# 2_-_IO_Socket_0.net
KiCad netlist of a schematic drawn in Altium Designer
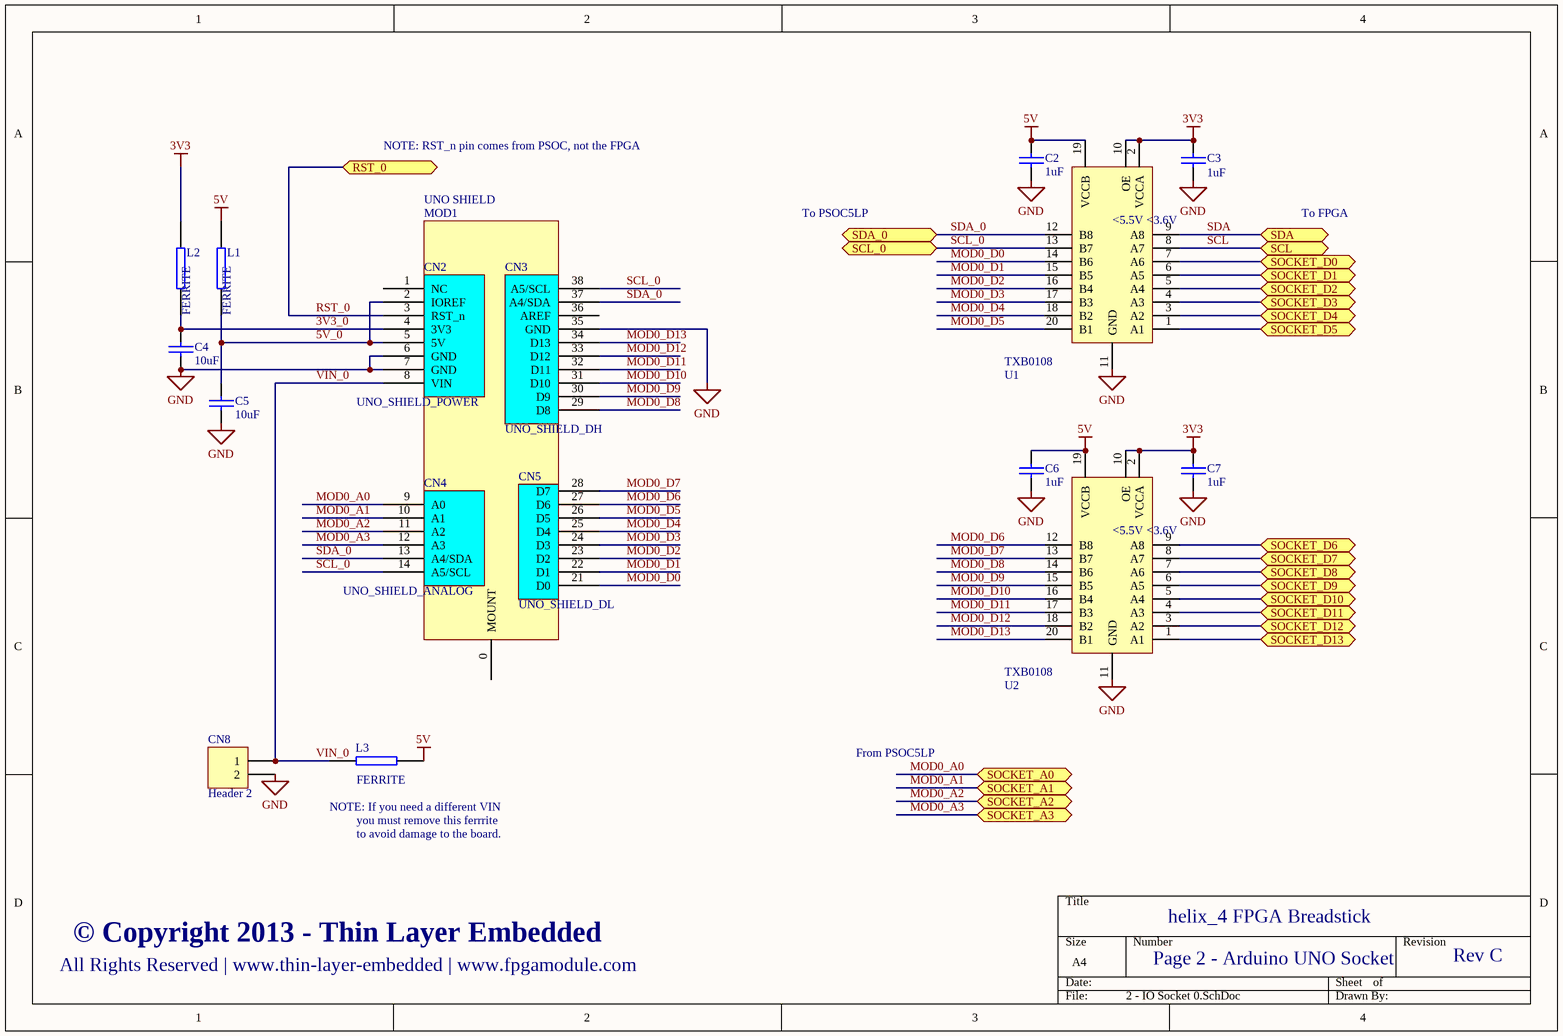
[diagram p0: 2 - IO Socket 0.SchDoc]

(export (version "E")
  (design (tool "Eeschema 10.0.6"))
  (components
    (comp (ref "C2")
      (value "1uF")
      (footprint "0805")
      (description "Capacitor")
      (libsource (lib "*") (part "CAP"))
    )
    (comp (ref "C3")
      (value "1uF")
      (footprint "0805")
      (description "Capacitor")
      (libsource (lib "*") (part "CAP"))
    )
    (comp (ref "C4")
      (value "10uF")
      (footprint "0805")
      (description "Capacitor")
      (libsource (lib "*") (part "CAP"))
    )
    (comp (ref "C5")
      (value "10uF")
      (footprint "0805")
      (description "Capacitor")
      (libsource (lib "*") (part "CAP"))
    )
    (comp (ref "C6")
      (value "1uF")
      (footprint "0805")
      (description "Capacitor")
      (libsource (lib "*") (part "CAP"))
    )
    (comp (ref "C7")
      (value "1uF")
      (footprint "0805")
      (description "Capacitor")
      (libsource (lib "*") (part "CAP"))
    )
    (comp (ref "CN2")
      (value "UNO_SHIELD_POWER")
      (footprint "UNO_SHIELD_POWER")
      (libsource (lib "master_library") (part "UNO_SHIELD_POWER"))
    )
    (comp (ref "CN3")
      (value "UNO_SHIELD_DH")
      (footprint "UNO_SHIELD_DH")
      (libsource (lib "master_library") (part "UNO_SHIELD_DH"))
    )
    (comp (ref "CN4")
      (value "UNO_SHIELD_ANALOG")
      (footprint "UNO_SHIELD_ANALOG")
      (libsource (lib "master_library") (part "UNO_SHIELD_ANALOG"))
    )
    (comp (ref "CN5")
      (value "UNO_SHIELD_DL")
      (footprint "UNO_SHIELD_DL")
      (libsource (lib "master_library") (part "UNO_SHIELD_DL"))
    )
    (comp (ref "CN8")
      (value "Header 2")
      (footprint "HDR1X2")
      (description "Header, 2-Pin")
      (fields (field (name "PUBLISHER") "Altium Limited"))
      (libsource (lib "Miscellaneous Connectors") (part "Header 2"))
    )
    (comp (ref "L1") (value "FERRITE") (footprint "0805") (libsource (lib "*") (part "FERRITE")))
    (comp (ref "L2") (value "FERRITE") (footprint "0805") (libsource (lib "*") (part "FERRITE")))
    (comp (ref "L3") (value "FERRITE") (footprint "0805") (libsource (lib "*") (part "FERRITE")))
    (comp (ref "MOD1")
      (value "UNO SHIELD")
      (footprint "UNO_SHIELD_MECH_NO_OUTLINE")
      (libsource (lib "master_library") (part "UNO_SHIELD_MECH"))
    )
    (comp (ref "U1")
      (value "TXB0108")
      (footprint "TSSOP20")
      (description "TI Bir-dir buffer")
      (libsource (lib "master_library") (part "TXB0108"))
    )
    (comp (ref "U2")
      (value "TXB0108")
      (footprint "TSSOP20")
      (description "TI Bir-dir buffer")
      (libsource (lib "master_library") (part "TXB0108"))
    )
  )
  (nets
    (net (code "1") (name "/3V3_0") (class "Default")
      (node (ref "C4") (pin "1") (pinfunction "1_1") (pintype "passive"))
      (node (ref "CN2") (pin "4") (pinfunction "3V3_4") (pintype "passive"))
      (node (ref "L2") (pin "2") (pinfunction "2_2") (pintype "passive"))
    )
    (net (code "2") (name "/5V_0") (class "Default")
      (node (ref "C5") (pin "1") (pinfunction "1_1") (pintype "passive"))
      (node (ref "CN2") (pin "2") (pinfunction "IOREF_2") (pintype "passive"))
      (node (ref "CN2") (pin "5") (pinfunction "5V_5") (pintype "passive"))
      (node (ref "L1") (pin "2") (pinfunction "2_2") (pintype "passive"))
    )
    (net (code "3") (name "/MOD0_A0") (class "Default")
      (node (ref "CN4") (pin "9") (pinfunction "A0_9") (pintype "passive"))
    )
    (net (code "4") (name "/MOD0_A1") (class "Default")
      (node (ref "CN4") (pin "10") (pinfunction "A1_10") (pintype "passive"))
    )
    (net (code "5") (name "/MOD0_A2") (class "Default")
      (node (ref "CN4") (pin "11") (pinfunction "A2_11") (pintype "passive"))
    )
    (net (code "6") (name "/MOD0_A3") (class "Default")
      (node (ref "CN4") (pin "12") (pinfunction "A3_12") (pintype "passive"))
    )
    (net (code "7") (name "/MOD0_D0") (class "Default")
      (node (ref "CN5") (pin "21") (pinfunction "D0_21") (pintype "passive"))
      (node (ref "U1") (pin "14") (pinfunction "B6_14") (pintype "passive"))
    )
    (net (code "8") (name "/MOD0_D1") (class "Default")
      (node (ref "CN5") (pin "22") (pinfunction "D1_22") (pintype "passive"))
      (node (ref "U1") (pin "15") (pinfunction "B5_15") (pintype "passive"))
    )
    (net (code "9") (name "/MOD0_D2") (class "Default")
      (node (ref "CN5") (pin "23") (pinfunction "D2_23") (pintype "passive"))
      (node (ref "U1") (pin "16") (pinfunction "B4_16") (pintype "passive"))
    )
    (net (code "10") (name "/MOD0_D3") (class "Default")
      (node (ref "CN5") (pin "24") (pinfunction "D3_24") (pintype "passive"))
      (node (ref "U1") (pin "17") (pinfunction "B3_17") (pintype "passive"))
    )
    (net (code "11") (name "/MOD0_D4") (class "Default")
      (node (ref "CN5") (pin "25") (pinfunction "D4_25") (pintype "passive"))
      (node (ref "U1") (pin "18") (pinfunction "B2_18") (pintype "passive"))
    )
    (net (code "12") (name "/MOD0_D5") (class "Default")
      (node (ref "CN5") (pin "26") (pinfunction "D5_26") (pintype "passive"))
      (node (ref "U1") (pin "20") (pinfunction "B1_20") (pintype "passive"))
    )
    (net (code "13") (name "/MOD0_D6") (class "Default")
      (node (ref "CN5") (pin "27") (pinfunction "D6_27") (pintype "passive"))
      (node (ref "U2") (pin "12") (pinfunction "B8_12") (pintype "passive"))
    )
    (net (code "14") (name "/MOD0_D7") (class "Default")
      (node (ref "CN5") (pin "28") (pinfunction "D7_28") (pintype "passive"))
      (node (ref "U2") (pin "13") (pinfunction "B7_13") (pintype "passive"))
    )
    (net (code "15") (name "/MOD0_D8") (class "Default")
      (node (ref "CN3") (pin "29") (pinfunction "D8_29") (pintype "passive"))
      (node (ref "U2") (pin "14") (pinfunction "B6_14") (pintype "passive"))
    )
    (net (code "16") (name "/MOD0_D9") (class "Default")
      (node (ref "CN3") (pin "30") (pinfunction "D9_30") (pintype "passive"))
      (node (ref "U2") (pin "15") (pinfunction "B5_15") (pintype "passive"))
    )
    (net (code "17") (name "/MOD0_D10") (class "Default")
      (node (ref "CN3") (pin "31") (pinfunction "D10_31") (pintype "passive"))
      (node (ref "U2") (pin "16") (pinfunction "B4_16") (pintype "passive"))
    )
    (net (code "18") (name "/MOD0_D11") (class "Default")
      (node (ref "CN3") (pin "32") (pinfunction "D11_32") (pintype "passive"))
      (node (ref "U2") (pin "17") (pinfunction "B3_17") (pintype "passive"))
    )
    (net (code "19") (name "/MOD0_D12") (class "Default")
      (node (ref "CN3") (pin "33") (pinfunction "D12_33") (pintype "passive"))
      (node (ref "U2") (pin "18") (pinfunction "B2_18") (pintype "passive"))
    )
    (net (code "20") (name "/MOD0_D13") (class "Default")
      (node (ref "CN3") (pin "34") (pinfunction "D13_34") (pintype "passive"))
      (node (ref "U2") (pin "20") (pinfunction "B1_20") (pintype "passive"))
    )
    (net (code "21") (name "/RST_0") (class "Default")
      (node (ref "CN2") (pin "3") (pinfunction "RST_n_3") (pintype "passive"))
    )
    (net (code "22") (name "/SCL") (class "Default")
      (node (ref "U1") (pin "8") (pinfunction "A7_8") (pintype "passive"))
    )
    (net (code "23") (name "/SCL_0") (class "Default")
      (node (ref "CN3") (pin "38") (pinfunction "A5/SCL_38") (pintype "passive"))
      (node (ref "CN4") (pin "14") (pinfunction "A5/SCL_14") (pintype "passive"))
      (node (ref "U1") (pin "13") (pinfunction "B7_13") (pintype "passive"))
    )
    (net (code "24") (name "/SDA") (class "Default")
      (node (ref "U1") (pin "9") (pinfunction "A8_9") (pintype "passive"))
    )
    (net (code "25") (name "/SDA_0") (class "Default")
      (node (ref "CN3") (pin "37") (pinfunction "A4/SDA_37") (pintype "passive"))
      (node (ref "CN4") (pin "13") (pinfunction "A4/SDA_13") (pintype "passive"))
      (node (ref "U1") (pin "12") (pinfunction "B8_12") (pintype "passive"))
    )
    (net (code "26") (name "/SOCKET_D0") (class "Default")
      (node (ref "U1") (pin "7") (pinfunction "A6_7") (pintype "passive"))
    )
    (net (code "27") (name "/SOCKET_D1") (class "Default")
      (node (ref "U1") (pin "6") (pinfunction "A5_6") (pintype "passive"))
    )
    (net (code "28") (name "/SOCKET_D2") (class "Default")
      (node (ref "U1") (pin "5") (pinfunction "A4_5") (pintype "passive"))
    )
    (net (code "29") (name "/SOCKET_D3") (class "Default")
      (node (ref "U1") (pin "4") (pinfunction "A3_4") (pintype "passive"))
    )
    (net (code "30") (name "/SOCKET_D4") (class "Default")
      (node (ref "U1") (pin "3") (pinfunction "A2_3") (pintype "passive"))
    )
    (net (code "31") (name "/SOCKET_D5") (class "Default")
      (node (ref "U1") (pin "1") (pinfunction "A1_1") (pintype "passive"))
    )
    (net (code "32") (name "/SOCKET_D6") (class "Default")
      (node (ref "U2") (pin "9") (pinfunction "A8_9") (pintype "passive"))
    )
    (net (code "33") (name "/SOCKET_D7") (class "Default")
      (node (ref "U2") (pin "8") (pinfunction "A7_8") (pintype "passive"))
    )
    (net (code "34") (name "/SOCKET_D8") (class "Default")
      (node (ref "U2") (pin "7") (pinfunction "A6_7") (pintype "passive"))
    )
    (net (code "35") (name "/SOCKET_D9") (class "Default")
      (node (ref "U2") (pin "6") (pinfunction "A5_6") (pintype "passive"))
    )
    (net (code "36") (name "/SOCKET_D10") (class "Default")
      (node (ref "U2") (pin "5") (pinfunction "A4_5") (pintype "passive"))
    )
    (net (code "37") (name "/SOCKET_D11") (class "Default")
      (node (ref "U2") (pin "4") (pinfunction "A3_4") (pintype "passive"))
    )
    (net (code "38") (name "/SOCKET_D12") (class "Default")
      (node (ref "U2") (pin "3") (pinfunction "A2_3") (pintype "passive"))
    )
    (net (code "39") (name "/SOCKET_D13") (class "Default")
      (node (ref "U2") (pin "1") (pinfunction "A1_1") (pintype "passive"))
    )
    (net (code "40") (name "/VIN_0") (class "Default")
      (node (ref "CN2") (pin "8") (pinfunction "VIN_8") (pintype "passive"))
      (node (ref "CN8") (pin "1") (pinfunction "1_1") (pintype "passive"))
      (node (ref "L3") (pin "2") (pinfunction "2_2") (pintype "passive"))
    )
    (net (code "41") (name "3V3") (class "Default")
      (node (ref "C3") (pin "2") (pinfunction "2_2") (pintype "passive"))
      (node (ref "C7") (pin "2") (pinfunction "2_2") (pintype "passive"))
      (node (ref "L2") (pin "1") (pinfunction "1_1") (pintype "passive"))
      (node (ref "U1") (pin "10") (pinfunction "OE_10") (pintype "passive"))
      (node (ref "U1") (pin "2") (pinfunction "VCCA_2") (pintype "passive"))
      (node (ref "U2") (pin "10") (pinfunction "OE_10") (pintype "passive"))
      (node (ref "U2") (pin "2") (pinfunction "VCCA_2") (pintype "passive"))
    )
    (net (code "42") (name "5V") (class "Default")
      (node (ref "C2") (pin "2") (pinfunction "2_2") (pintype "passive"))
      (node (ref "C6") (pin "2") (pinfunction "2_2") (pintype "passive"))
      (node (ref "L1") (pin "1") (pinfunction "1_1") (pintype "passive"))
      (node (ref "L3") (pin "1") (pinfunction "1_1") (pintype "passive"))
      (node (ref "U1") (pin "19") (pinfunction "VCCB_19") (pintype "passive"))
      (node (ref "U2") (pin "19") (pinfunction "VCCB_19") (pintype "passive"))
    )
    (net (code "43") (name "GND") (class "Default")
      (node (ref "C2") (pin "1") (pinfunction "1_1") (pintype "passive"))
      (node (ref "C3") (pin "1") (pinfunction "1_1") (pintype "passive"))
      (node (ref "C4") (pin "2") (pinfunction "2_2") (pintype "passive"))
      (node (ref "C5") (pin "2") (pinfunction "2_2") (pintype "passive"))
      (node (ref "C6") (pin "1") (pinfunction "1_1") (pintype "passive"))
      (node (ref "C7") (pin "1") (pinfunction "1_1") (pintype "passive"))
      (node (ref "CN2") (pin "6") (pinfunction "GND_6") (pintype "passive"))
      (node (ref "CN2") (pin "7") (pinfunction "GND_7") (pintype "passive"))
      (node (ref "CN3") (pin "35") (pinfunction "GND_35") (pintype "passive"))
      (node (ref "CN8") (pin "2") (pinfunction "2_2") (pintype "passive"))
      (node (ref "U1") (pin "11") (pinfunction "GND_11") (pintype "passive"))
      (node (ref "U2") (pin "11") (pinfunction "GND_11") (pintype "passive"))
    )
    (net (code "44") (name "unconnected-(CN2-NC-Pad1)") (class "Default")
      (node (ref "CN2") (pin "1") (pinfunction "NC_1") (pintype "passive"))
    )
    (net (code "45") (name "unconnected-(CN3-AREF-Pad36)") (class "Default")
      (node (ref "CN3") (pin "36") (pinfunction "AREF_36") (pintype "passive"))
    )
    (net (code "46") (name "unconnected-(MOD1-MOUNT-Pad0)") (class "Default")
      (node (ref "MOD1") (pin "0") (pinfunction "MOUNT_0") (pintype "passive"))
    )
  )
)
